# 12V_DC-DC_ISOLATOR.net
KiCad netlist of a schematic drawn in Altium Designer
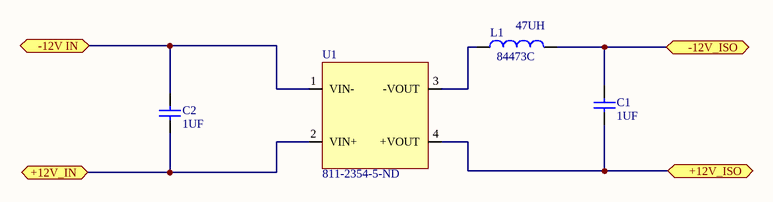
[diagram p0: 12V DC-DC ISOLATOR.SchDoc]

(export (version "E")
  (design (tool "Eeschema 10.0.6"))
  (components
    (comp (ref "C1")
      (value "CC0805JKX7R9BB105")
      (footprint "CAP0805_NEW")
      (description "CAP CER 1UF 50V X7R 0805")
      (fields
        (field (name "MANUFACTURER") "Yageo")
        (field (name "TOLERANCE") "±5%")
        (field (name "CAPACITANCE") "1UF")
      )
      (libsource (lib "ucc28180-V04") (part "CC0805JKX7R9BB105"))
    )
    (comp (ref "C2")
      (value "CC0805JKX7R9BB105")
      (footprint "CAP0805_NEW")
      (description "CAP CER 1UF 50V X7R 0805")
      (fields
        (field (name "MANUFACTURER") "Yageo")
        (field (name "TOLERANCE") "±5%")
        (field (name "CAPACITANCE") "1UF")
      )
      (libsource (lib "ucc28180-V04") (part "CC0805JKX7R9BB105"))
    )
    (comp (ref "L1")
      (value "84473C")
      (footprint "INDC5435X06N")
      (description "FIXED IND 47UH 420MA 1.1 OHM")
      (fields
        (field (name "MANUFACTURER") "Murata Power Solutions Inc.")
        (field (name "MANUFACTURER PART NUMBER") "84473C")
        (field (name "TOLERANCE") "±10%")
        (field (name "INDUCTANCE") "47UH")
      )
      (libsource (lib "ucc28180-V04") (part "84473C"))
    )
    (comp (ref "U1")
      (value "MEE3S1212SC")
      (footprint "MEE3S1212SC")
      (description "DC/DC CONVERTER 12V 3W ISOLATED")
      (fields
        (field (name "MANUFACTURER") "Murata Power Solutions Inc.")
        (field (name "SUPPLIER PART NUMBER 1") "811-2354-5-ND")
      )
      (libsource (lib "ucc28180-V04") (part "MEE3S1212SC"))
    )
  )
  (nets
    (net (code "1") (name "/+12V_IN") (class "Default")
      (node (ref "C2") (pin "1") (pinfunction "1_1") (pintype "passive"))
      (node (ref "U1") (pin "2") (pinfunction "VIN+_2") (pintype "passive"))
    )
    (net (code "2") (name "/+12V_ISO") (class "Default")
      (node (ref "C1") (pin "1") (pinfunction "1_1") (pintype "passive"))
      (node (ref "U1") (pin "4") (pinfunction "+VOUT_4") (pintype "passive"))
    )
    (net (code "3") (name "/-12V IN") (class "Default")
      (node (ref "C2") (pin "2") (pinfunction "2_2") (pintype "passive"))
      (node (ref "U1") (pin "1") (pinfunction "VIN-_1") (pintype "passive"))
    )
    (net (code "4") (name "/-12V_ISO") (class "Default")
      (node (ref "C1") (pin "2") (pinfunction "2_2") (pintype "passive"))
      (node (ref "L1") (pin "2") (pinfunction "2_2") (pintype "passive"))
    )
    (net (code "5") (name "Net-(U1--VOUT)") (class "Default")
      (node (ref "L1") (pin "1") (pinfunction "1_1") (pintype "passive"))
      (node (ref "U1") (pin "3") (pinfunction "-VOUT_3") (pintype "passive"))
    )
  )
)
